# CDi.net
KiCad netlist of a schematic drawn in EAGLE
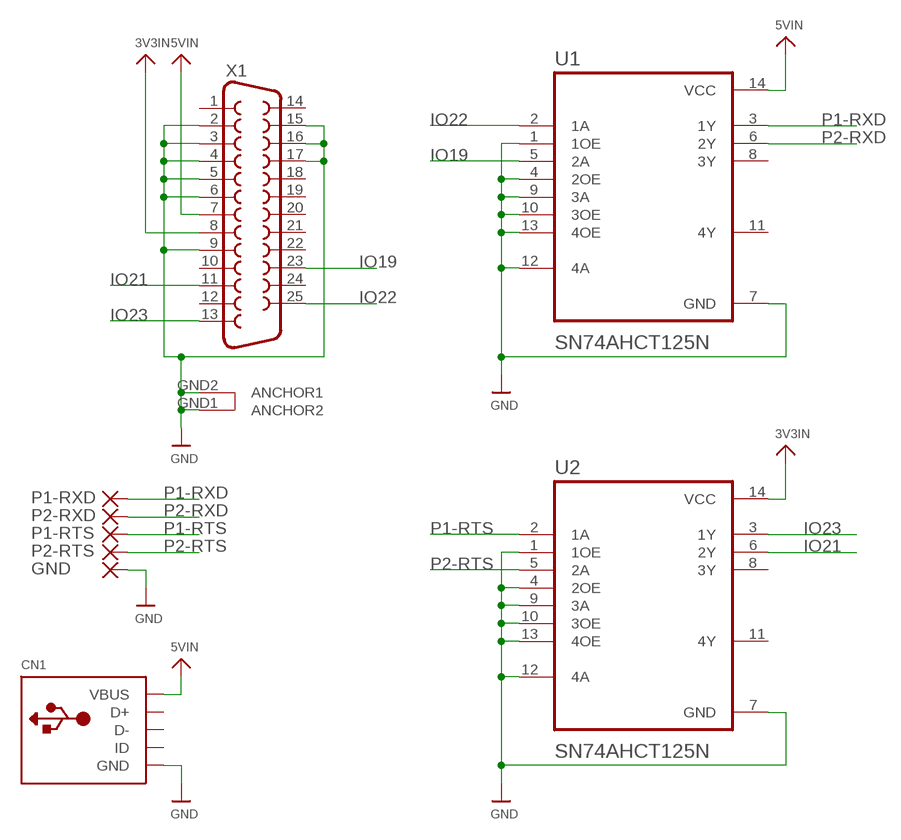
[diagram p0: schematic, sheet 1]

(export (version "E")
  (design (tool "Eeschema 10.0.6"))
  (components
    (comp (ref "CN1")
      (value "USBTHM")
      (footprint "eagle-import:USB-MINIB-THM")
      (libsource (lib "eagle-import") (part "USBTHM"))
    )
    (comp (ref "GND")
      (value "SMD5")
      (footprint "eagle-import:SMD2,54-5,08")
      (libsource (lib "eagle-import") (part "SMD5"))
    )
    (comp (ref "P1-RTS")
      (value "SMD5")
      (footprint "eagle-import:SMD2,54-5,08")
      (libsource (lib "eagle-import") (part "SMD5"))
    )
    (comp (ref "P1-RXD")
      (value "SMD5")
      (footprint "eagle-import:SMD2,54-5,08")
      (libsource (lib "eagle-import") (part "SMD5"))
    )
    (comp (ref "P2-RTS")
      (value "SMD5")
      (footprint "eagle-import:SMD2,54-5,08")
      (libsource (lib "eagle-import") (part "SMD5"))
    )
    (comp (ref "P2-RXD")
      (value "SMD5")
      (footprint "eagle-import:SMD2,54-5,08")
      (libsource (lib "eagle-import") (part "SMD5"))
    )
    (comp (ref "U1")
      (value "SN74AHCT125N")
      (footprint "eagle-import:DIP794W45P254L1969H508Q14")
      (fields (field (name "MF") "Texas Instruments"))
      (libsource (lib "eagle-import") (part "SN74AHCT125N"))
    )
    (comp (ref "U2")
      (value "SN74AHCT125N")
      (footprint "eagle-import:DIP794W45P254L1969H508Q14")
      (fields (field (name "MF") "Texas Instruments"))
      (libsource (lib "eagle-import") (part "SN74AHCT125N"))
    )
    (comp (ref "X1")
      (value "DB25_FEMALEHP")
      (footprint "eagle-import:F25HP")
      (libsource (lib "eagle-import") (part "DB25_FEMALEHP"))
    )
  )
  (nets
    (net (code "1") (name "/IO19") (class "Default")
      (node (ref "U1") (pin "5") (pinfunction "2A_5") (pintype "input"))
      (node (ref "X1") (pin "23") (pinfunction "23_23") (pintype "passive"))
    )
    (net (code "2") (name "/IO21") (class "Default")
      (node (ref "U2") (pin "6") (pinfunction "2Y_6") (pintype "output"))
      (node (ref "X1") (pin "11") (pinfunction "11_11") (pintype "passive"))
    )
    (net (code "3") (name "/IO22") (class "Default")
      (node (ref "U1") (pin "2") (pinfunction "1A_2") (pintype "input"))
      (node (ref "X1") (pin "25") (pinfunction "25_25") (pintype "passive"))
    )
    (net (code "4") (name "/IO23") (class "Default")
      (node (ref "U2") (pin "3") (pinfunction "1Y_3") (pintype "output"))
      (node (ref "X1") (pin "13") (pinfunction "13_13") (pintype "passive"))
    )
    (net (code "5") (name "/P1-RTS") (class "Default")
      (node (ref "P1-RTS") (pin "1") (pinfunction "P_1") (pintype "passive"))
      (node (ref "U2") (pin "2") (pinfunction "1A_2") (pintype "input"))
    )
    (net (code "6") (name "/P1-RXD") (class "Default")
      (node (ref "P1-RXD") (pin "1") (pinfunction "P_1") (pintype "passive"))
      (node (ref "U1") (pin "3") (pinfunction "1Y_3") (pintype "output"))
    )
    (net (code "7") (name "/P2-RTS") (class "Default")
      (node (ref "P2-RTS") (pin "1") (pinfunction "P_1") (pintype "passive"))
      (node (ref "U2") (pin "5") (pinfunction "2A_5") (pintype "input"))
    )
    (net (code "8") (name "/P2-RXD") (class "Default")
      (node (ref "P2-RXD") (pin "1") (pinfunction "P_1") (pintype "passive"))
      (node (ref "U1") (pin "6") (pinfunction "2Y_6") (pintype "output"))
    )
    (net (code "9") (name "3V3IN") (class "Default")
      (node (ref "U2") (pin "14") (pinfunction "VCC_14") (pintype "power_in"))
      (node (ref "X1") (pin "8") (pinfunction "8_8") (pintype "passive"))
    )
    (net (code "10") (name "5VIN") (class "Default")
      (node (ref "CN1") (pin "VBUS") (pinfunction "VBUS_VBUS") (pintype "power_in"))
      (node (ref "U1") (pin "14") (pinfunction "VCC_14") (pintype "power_in"))
      (node (ref "X1") (pin "7") (pinfunction "7_7") (pintype "passive"))
    )
    (net (code "11") (name "GND") (class "Default")
      (node (ref "CN1") (pin "GND") (pinfunction "GND_GND") (pintype "power_in"))
      (node (ref "GND") (pin "1") (pinfunction "P_1") (pintype "passive"))
      (node (ref "U1") (pin "1") (pinfunction "1OE_1") (pintype "input"))
      (node (ref "U1") (pin "10") (pinfunction "3OE_10") (pintype "input"))
      (node (ref "U1") (pin "12") (pinfunction "4A_12") (pintype "bidirectional"))
      (node (ref "U1") (pin "13") (pinfunction "4OE_13") (pintype "input"))
      (node (ref "U1") (pin "4") (pinfunction "2OE_4") (pintype "input"))
      (node (ref "U1") (pin "7") (pinfunction "GND_7") (pintype "power_in"))
      (node (ref "U1") (pin "9") (pinfunction "3A_9") (pintype "input"))
      (node (ref "U2") (pin "1") (pinfunction "1OE_1") (pintype "input"))
      (node (ref "U2") (pin "10") (pinfunction "3OE_10") (pintype "input"))
      (node (ref "U2") (pin "12") (pinfunction "4A_12") (pintype "bidirectional"))
      (node (ref "U2") (pin "13") (pinfunction "4OE_13") (pintype "input"))
      (node (ref "U2") (pin "4") (pinfunction "2OE_4") (pintype "input"))
      (node (ref "U2") (pin "7") (pinfunction "GND_7") (pintype "power_in"))
      (node (ref "U2") (pin "9") (pinfunction "3A_9") (pintype "input"))
      (node (ref "X1") (pin "15") (pinfunction "15_15") (pintype "passive"))
      (node (ref "X1") (pin "16") (pinfunction "16_16") (pintype "passive"))
      (node (ref "X1") (pin "17") (pinfunction "17_17") (pintype "passive"))
      (node (ref "X1") (pin "2") (pinfunction "2_2") (pintype "passive"))
      (node (ref "X1") (pin "3") (pinfunction "3_3") (pintype "passive"))
      (node (ref "X1") (pin "4") (pinfunction "4_4") (pintype "passive"))
      (node (ref "X1") (pin "5") (pinfunction "5_5") (pintype "passive"))
      (node (ref "X1") (pin "6") (pinfunction "6_6") (pintype "passive"))
      (node (ref "X1") (pin "9") (pinfunction "9_9") (pintype "passive"))
      (node (ref "X1") (pin "GND1") (pinfunction "ANCHOR2_GND1") (pintype "bidirectional"))
      (node (ref "X1") (pin "GND2") (pinfunction "ANCHOR1_GND2") (pintype "bidirectional"))
    )
    (net (code "12") (name "unconnected-(CN1-PadD+)") (class "Default")
      (node (ref "CN1") (pin "D+") (pinfunction "D+_D+") (pintype "bidirectional"))
    )
    (net (code "13") (name "unconnected-(CN1-PadD-)") (class "Default")
      (node (ref "CN1") (pin "D-") (pinfunction "D-_D-") (pintype "bidirectional"))
    )
    (net (code "14") (name "unconnected-(CN1-PadID)") (class "Default")
      (node (ref "CN1") (pin "ID") (pinfunction "ID_ID") (pintype "bidirectional"))
    )
    (net (code "15") (name "unconnected-(U1-3Y-Pad8)") (class "Default")
      (node (ref "U1") (pin "8") (pinfunction "3Y_8") (pintype "output"))
    )
    (net (code "16") (name "unconnected-(U1-4Y-Pad11)") (class "Default")
      (node (ref "U1") (pin "11") (pinfunction "4Y_11") (pintype "output"))
    )
    (net (code "17") (name "unconnected-(U2-3Y-Pad8)") (class "Default")
      (node (ref "U2") (pin "8") (pinfunction "3Y_8") (pintype "output"))
    )
    (net (code "18") (name "unconnected-(U2-4Y-Pad11)") (class "Default")
      (node (ref "U2") (pin "11") (pinfunction "4Y_11") (pintype "output"))
    )
    (net (code "19") (name "unconnected-(X1-Pad1)") (class "Default")
      (node (ref "X1") (pin "1") (pinfunction "1_1") (pintype "passive"))
    )
    (net (code "20") (name "unconnected-(X1-Pad10)") (class "Default")
      (node (ref "X1") (pin "10") (pinfunction "10_10") (pintype "passive"))
    )
    (net (code "21") (name "unconnected-(X1-Pad12)") (class "Default")
      (node (ref "X1") (pin "12") (pinfunction "12_12") (pintype "passive"))
    )
    (net (code "22") (name "unconnected-(X1-Pad14)") (class "Default")
      (node (ref "X1") (pin "14") (pinfunction "14_14") (pintype "passive"))
    )
    (net (code "23") (name "unconnected-(X1-Pad18)") (class "Default")
      (node (ref "X1") (pin "18") (pinfunction "18_18") (pintype "passive"))
    )
    (net (code "24") (name "unconnected-(X1-Pad19)") (class "Default")
      (node (ref "X1") (pin "19") (pinfunction "19_19") (pintype "passive"))
    )
    (net (code "25") (name "unconnected-(X1-Pad20)") (class "Default")
      (node (ref "X1") (pin "20") (pinfunction "20_20") (pintype "passive"))
    )
    (net (code "26") (name "unconnected-(X1-Pad21)") (class "Default")
      (node (ref "X1") (pin "21") (pinfunction "21_21") (pintype "passive"))
    )
    (net (code "27") (name "unconnected-(X1-Pad22)") (class "Default")
      (node (ref "X1") (pin "22") (pinfunction "22_22") (pintype "passive"))
    )
    (net (code "28") (name "unconnected-(X1-Pad24)") (class "Default")
      (node (ref "X1") (pin "24") (pinfunction "24_24") (pintype "passive"))
    )
  )
)
